# MCU_SWD_Program.net
KiCad netlist of a schematic drawn in Altium Designer
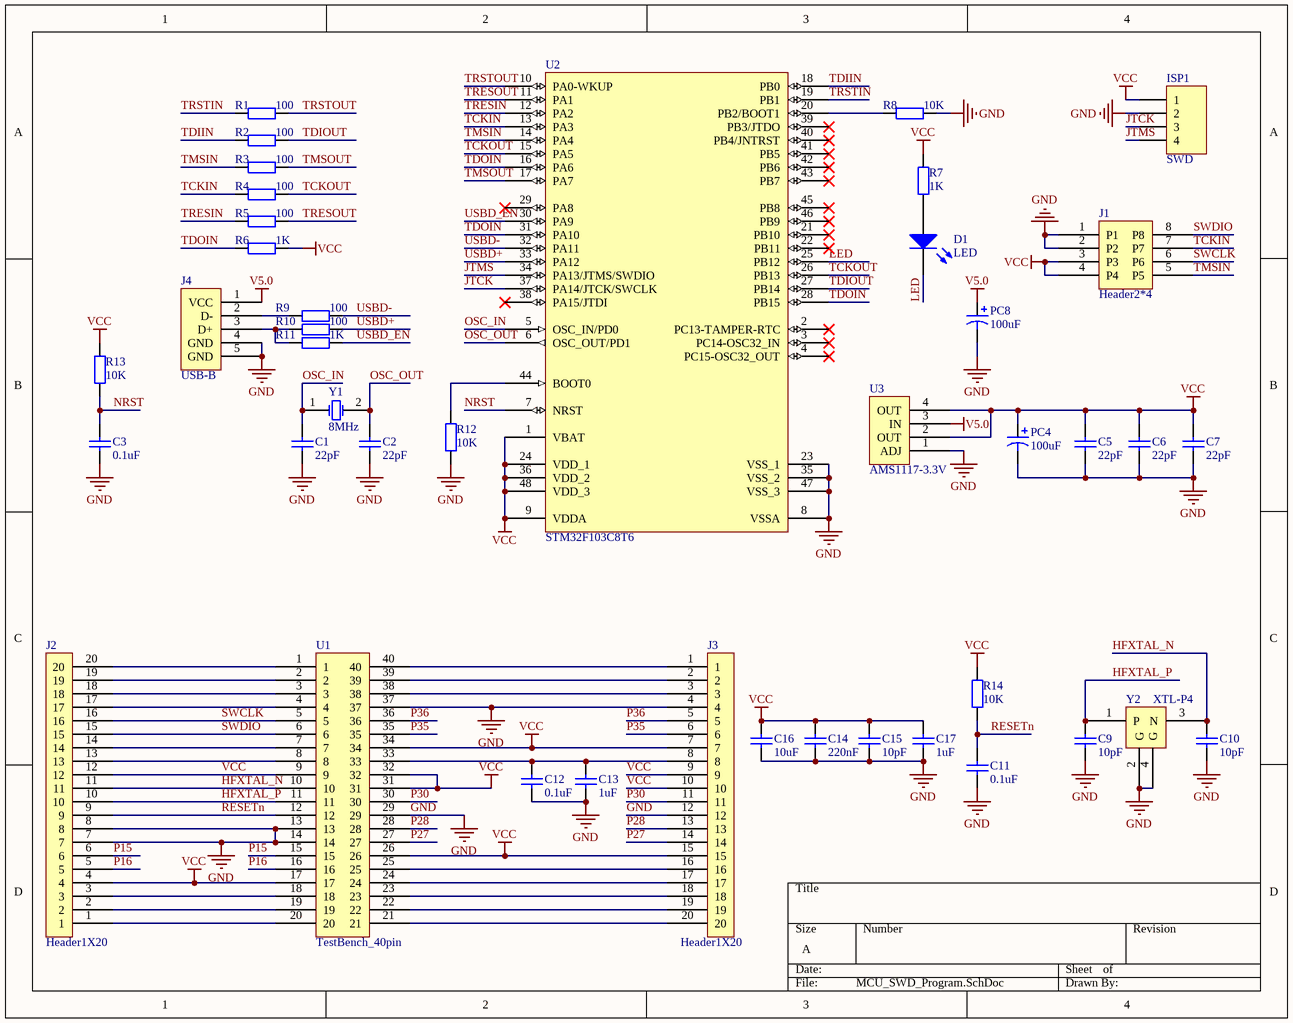
[diagram p0: MCU_SWD_Program.SchDoc]

(export (version "E")
  (design (tool "Eeschema 10.0.6"))
  (components
    (comp (ref "C1")
      (value "22pF")
      (footprint "C0603")
      (description "Capacitor")
      (fields (field (name "PUBLISHER") "Altium Limited"))
      (libsource (lib "Miscellaneous Devices") (part "Cap"))
    )
    (comp (ref "C2")
      (value "22pF")
      (footprint "C0603")
      (description "Capacitor")
      (fields (field (name "PUBLISHER") "Altium Limited"))
      (libsource (lib "Miscellaneous Devices") (part "Cap"))
    )
    (comp (ref "C3")
      (value "0.1uF")
      (footprint "C0603")
      (description "Capacitor")
      (fields (field (name "PUBLISHER") "Altium Limited"))
      (libsource (lib "Miscellaneous Devices") (part "Cap"))
    )
    (comp (ref "C5")
      (value "22pF")
      (footprint "C0603")
      (description "Capacitor")
      (fields (field (name "PUBLISHER") "Altium Limited"))
      (libsource (lib "Miscellaneous Devices") (part "Cap"))
    )
    (comp (ref "C6")
      (value "22pF")
      (footprint "C0603")
      (description "Capacitor")
      (fields (field (name "PUBLISHER") "Altium Limited"))
      (libsource (lib "Miscellaneous Devices") (part "Cap"))
    )
    (comp (ref "C7")
      (value "22pF")
      (footprint "C0603")
      (description "Capacitor")
      (fields (field (name "PUBLISHER") "Altium Limited"))
      (libsource (lib "Miscellaneous Devices") (part "Cap"))
    )
    (comp (ref "C9")
      (value "10pF")
      (footprint "C0603")
      (description "Capacitor")
      (fields (field (name "PUBLISHER") "Altium Limited"))
      (libsource (lib "Miscellaneous Devices") (part "Cap"))
    )
    (comp (ref "C10")
      (value "10pF")
      (footprint "C0603")
      (description "Capacitor")
      (fields (field (name "PUBLISHER") "Altium Limited"))
      (libsource (lib "Miscellaneous Devices") (part "Cap"))
    )
    (comp (ref "C11")
      (value "0.1uF")
      (footprint "C0603")
      (description "Capacitor")
      (fields (field (name "PUBLISHER") "Altium Limited"))
      (libsource (lib "Miscellaneous Devices") (part "Cap"))
    )
    (comp (ref "C12")
      (value "0.1uF")
      (footprint "C0603")
      (description "Capacitor")
      (fields (field (name "PUBLISHER") "Altium Limited"))
      (libsource (lib "Miscellaneous Devices") (part "Cap"))
    )
    (comp (ref "C13")
      (value "1uF")
      (footprint "C0603")
      (description "Capacitor")
      (fields (field (name "PUBLISHER") "Altium Limited"))
      (libsource (lib "Miscellaneous Devices") (part "Cap"))
    )
    (comp (ref "C14")
      (value "220nF")
      (footprint "C0603")
      (description "Capacitor")
      (fields (field (name "PUBLISHER") "Altium Limited"))
      (libsource (lib "Miscellaneous Devices") (part "Cap"))
    )
    (comp (ref "C15")
      (value "10pF")
      (footprint "C0603")
      (description "Capacitor")
      (fields (field (name "PUBLISHER") "Altium Limited"))
      (libsource (lib "Miscellaneous Devices") (part "Cap"))
    )
    (comp (ref "C16")
      (value "10uF")
      (footprint "C0603")
      (description "Capacitor")
      (fields (field (name "PUBLISHER") "Altium Limited"))
      (libsource (lib "Miscellaneous Devices") (part "Cap"))
    )
    (comp (ref "C17")
      (value "1uF")
      (footprint "C0603")
      (description "Capacitor")
      (fields (field (name "PUBLISHER") "Altium Limited"))
      (libsource (lib "Miscellaneous Devices") (part "Cap"))
    )
    (comp (ref "D1")
      (value "LED")
      (footprint "D-0805")
      (description "Typical RED, GREEN, YELLOW, AMBER GaAs LED")
      (fields (field (name "PUBLISHER") "Altium Limited"))
      (libsource (lib "Miscellaneous Devices") (part "LED2"))
    )
    (comp (ref "ISP1")
      (value "SWD")
      (footprint "HDR1X4")
      (description "Header, 4-Pin")
      (fields (field (name "PUBLISHER") "Altium Limited"))
      (libsource (lib "Miscellaneous Connectors") (part "Header 4"))
    )
    (comp (ref "J1")
      (value "Header2*4")
      (footprint "HDR2X4")
      (libsource (lib "GavinPCBLib") (part "Header2X4"))
    )
    (comp (ref "J2")
      (value "Header1X20")
      (footprint "HDR2.54-1X20")
      (libsource (lib "GavinPCBLib") (part "Header1X20"))
    )
    (comp (ref "J3")
      (value "Header1X20")
      (footprint "HDR2.54-1X20")
      (libsource (lib "") (part "Header1X20_1"))
    )
    (comp (ref "J4") (value "USB-B") (footprint "USB-B") (libsource (lib "GavinPCBLib") (part "USB-B")))
    (comp (ref "PC4")
      (value "100uF")
      (footprint "C1206")
      (description "Polarized Capacitor (Surface Mount)")
      (fields (field (name "PUBLISHER") "Altium Limited"))
      (libsource (lib "Miscellaneous Devices") (part "Cap Pol3"))
    )
    (comp (ref "PC8")
      (value "100uF")
      (footprint "C1206")
      (description "Polarized Capacitor (Surface Mount)")
      (fields (field (name "PUBLISHER") "Altium Limited"))
      (libsource (lib "Miscellaneous Devices") (part "Cap Pol3"))
    )
    (comp (ref "R1")
      (value "100")
      (footprint "R0603")
      (description "Resistor")
      (fields (field (name "PUBLISHER") "Altium Limited"))
      (libsource (lib "Miscellaneous Devices") (part "Res2"))
    )
    (comp (ref "R2")
      (value "100")
      (footprint "R0603")
      (description "Resistor")
      (fields (field (name "PUBLISHER") "Altium Limited"))
      (libsource (lib "Miscellaneous Devices") (part "Res2"))
    )
    (comp (ref "R3")
      (value "100")
      (footprint "R0603")
      (description "Resistor")
      (fields (field (name "PUBLISHER") "Altium Limited"))
      (libsource (lib "Miscellaneous Devices") (part "Res2"))
    )
    (comp (ref "R4")
      (value "100")
      (footprint "R0603")
      (description "Resistor")
      (fields (field (name "PUBLISHER") "Altium Limited"))
      (libsource (lib "Miscellaneous Devices") (part "Res2"))
    )
    (comp (ref "R5")
      (value "100")
      (footprint "R0603")
      (description "Resistor")
      (fields (field (name "PUBLISHER") "Altium Limited"))
      (libsource (lib "Miscellaneous Devices") (part "Res2"))
    )
    (comp (ref "R6")
      (value "1K")
      (footprint "r0603")
      (description "Resistor")
      (fields (field (name "PUBLISHER") "Altium Limited"))
      (libsource (lib "Miscellaneous Devices") (part "Res2"))
    )
    (comp (ref "R7")
      (value "1K")
      (footprint "R0603")
      (description "Resistor")
      (fields (field (name "PUBLISHER") "Altium Limited"))
      (libsource (lib "") (part "Res2_1"))
    )
    (comp (ref "R8")
      (value "10K")
      (footprint "R0603")
      (description "Resistor")
      (fields (field (name "PUBLISHER") "Altium Limited"))
      (libsource (lib "Miscellaneous Devices") (part "Res2"))
    )
    (comp (ref "R9")
      (value "100")
      (footprint "R0603")
      (description "Resistor")
      (fields (field (name "PUBLISHER") "Altium Limited"))
      (libsource (lib "Miscellaneous Devices") (part "Res2"))
    )
    (comp (ref "R10")
      (value "100")
      (footprint "R0603")
      (description "Resistor")
      (fields (field (name "PUBLISHER") "Altium Limited"))
      (libsource (lib "Miscellaneous Devices") (part "Res2"))
    )
    (comp (ref "R11")
      (value "1K")
      (footprint "R0603")
      (description "Resistor")
      (fields (field (name "PUBLISHER") "Altium Limited"))
      (libsource (lib "Miscellaneous Devices") (part "Res2"))
    )
    (comp (ref "R12")
      (value "10K")
      (footprint "R0603")
      (description "Resistor")
      (fields (field (name "PUBLISHER") "Altium Limited"))
      (libsource (lib "") (part "Res2_2"))
    )
    (comp (ref "R13")
      (value "10K")
      (footprint "R0603")
      (description "Resistor")
      (fields (field (name "PUBLISHER") "Altium Limited"))
      (libsource (lib "") (part "Res2_1"))
    )
    (comp (ref "R14")
      (value "10K")
      (footprint "R0603")
      (description "Resistor")
      (fields (field (name "PUBLISHER") "Altium Limited"))
      (libsource (lib "") (part "Res2_1"))
    )
    (comp (ref "U1")
      (value "TestBench_40pin")
      (footprint "DIP40")
      (libsource (lib "GavinPCBLib") (part "TestBench_40pin"))
    )
    (comp (ref "U2")
      (value "STM32F103C8T6")
      (footprint "LQFP-48")
      (libsource (lib "GavinPCBLib") (part "STM32F103C8T6"))
    )
    (comp (ref "U3")
      (value "AMS1117-3.3V")
      (footprint "SOT-223")
      (libsource (lib "GavinPCBLib") (part "AMS1117-3.3V"))
    )
    (comp (ref "Y1")
      (value "8MHz")
      (footprint "XTAL-SMD2")
      (description "Crystal Oscillator")
      (fields (field (name "PUBLISHER") "Altium Limited"))
      (libsource (lib "Miscellaneous Devices") (part "XTAL"))
    )
    (comp (ref "Y2") (value "XTL-P4") (footprint "X3225") (libsource (lib "GavinPCBLib") (part "XTL-P4")))
  )
  (nets
    (net (code "1") (name "/HFXTAL_N") (class "Default")
      (node (ref "C10") (pin "1") (pinfunction "1_1") (pintype "passive"))
      (node (ref "J2") (pin "11") (pinfunction "11_11") (pintype "passive"))
      (node (ref "U1") (pin "10") (pinfunction "10_10") (pintype "passive"))
      (node (ref "Y2") (pin "3") (pinfunction "N_3") (pintype "passive"))
    )
    (net (code "2") (name "/HFXTAL_P") (class "Default")
      (node (ref "C9") (pin "1") (pinfunction "1_1") (pintype "passive"))
      (node (ref "J2") (pin "10") (pinfunction "10_10") (pintype "passive"))
      (node (ref "U1") (pin "11") (pinfunction "11_11") (pintype "passive"))
      (node (ref "Y2") (pin "1") (pinfunction "P_1") (pintype "passive"))
    )
    (net (code "3") (name "/JTCK") (class "Default")
      (node (ref "ISP1") (pin "3") (pinfunction "3_3") (pintype "passive"))
      (node (ref "U2") (pin "37") (pinfunction "PA14/JTCK/SWCLK_37") (pintype "bidirectional"))
    )
    (net (code "4") (name "/JTMS") (class "Default")
      (node (ref "ISP1") (pin "4") (pinfunction "4_4") (pintype "passive"))
      (node (ref "U2") (pin "34") (pinfunction "PA13/JTMS/SWDIO_34") (pintype "bidirectional"))
    )
    (net (code "5") (name "/LED") (class "Default")
      (node (ref "D1") (pin "2") (pinfunction "K_2") (pintype "passive"))
      (node (ref "U2") (pin "25") (pinfunction "PB12_25") (pintype "bidirectional"))
    )
    (net (code "6") (name "/NRST") (class "Default")
      (node (ref "C3") (pin "1") (pinfunction "1_1") (pintype "passive"))
      (node (ref "R13") (pin "1") (pinfunction "1_1") (pintype "passive"))
      (node (ref "U2") (pin "7") (pinfunction "NRST_7") (pintype "bidirectional"))
    )
    (net (code "7") (name "/OSC_IN") (class "Default")
      (node (ref "C1") (pin "1") (pinfunction "1_1") (pintype "passive"))
      (node (ref "U2") (pin "5") (pinfunction "OSC_IN/PD0_5") (pintype "input"))
      (node (ref "Y1") (pin "1") (pinfunction "OSC1_1") (pintype "passive"))
    )
    (net (code "8") (name "/OSC_OUT") (class "Default")
      (node (ref "C2") (pin "1") (pinfunction "1_1") (pintype "passive"))
      (node (ref "U2") (pin "6") (pinfunction "OSC_OUT/PD1_6") (pintype "output"))
      (node (ref "Y1") (pin "2") (pinfunction "OSC2_2") (pintype "passive"))
    )
    (net (code "9") (name "/P15") (class "Default")
      (node (ref "J2") (pin "6") (pinfunction "6_6") (pintype "passive"))
      (node (ref "U1") (pin "15") (pinfunction "15_15") (pintype "passive"))
    )
    (net (code "10") (name "/P16") (class "Default")
      (node (ref "J2") (pin "5") (pinfunction "5_5") (pintype "passive"))
      (node (ref "U1") (pin "16") (pinfunction "16_16") (pintype "passive"))
    )
    (net (code "11") (name "/P27") (class "Default")
      (node (ref "J3") (pin "14") (pinfunction "14_14") (pintype "passive"))
      (node (ref "U1") (pin "27") (pinfunction "27_27") (pintype "passive"))
    )
    (net (code "12") (name "/P28") (class "Default")
      (node (ref "J3") (pin "13") (pinfunction "13_13") (pintype "passive"))
      (node (ref "U1") (pin "28") (pinfunction "28_28") (pintype "passive"))
    )
    (net (code "13") (name "/P30") (class "Default")
      (node (ref "J3") (pin "11") (pinfunction "11_11") (pintype "passive"))
      (node (ref "U1") (pin "30") (pinfunction "30_30") (pintype "passive"))
    )
    (net (code "14") (name "/P35") (class "Default")
      (node (ref "J3") (pin "6") (pinfunction "6_6") (pintype "passive"))
      (node (ref "U1") (pin "35") (pinfunction "35_35") (pintype "passive"))
    )
    (net (code "15") (name "/P36") (class "Default")
      (node (ref "J3") (pin "5") (pinfunction "5_5") (pintype "passive"))
      (node (ref "U1") (pin "36") (pinfunction "36_36") (pintype "passive"))
    )
    (net (code "16") (name "/RESETn") (class "Default")
      (node (ref "C11") (pin "1") (pinfunction "1_1") (pintype "passive"))
      (node (ref "J2") (pin "9") (pinfunction "9_9") (pintype "passive"))
      (node (ref "R14") (pin "1") (pinfunction "1_1") (pintype "passive"))
      (node (ref "U1") (pin "12") (pinfunction "12_12") (pintype "passive"))
    )
    (net (code "17") (name "/SWCLK") (class "Default")
      (node (ref "J1") (pin "6") (pinfunction "P6_6") (pintype "passive"))
      (node (ref "J2") (pin "16") (pinfunction "16_16") (pintype "passive"))
      (node (ref "U1") (pin "5") (pinfunction "5_5") (pintype "passive"))
    )
    (net (code "18") (name "/SWDIO") (class "Default")
      (node (ref "J1") (pin "8") (pinfunction "P8_8") (pintype "passive"))
      (node (ref "J2") (pin "15") (pinfunction "15_15") (pintype "passive"))
      (node (ref "U1") (pin "6") (pinfunction "6_6") (pintype "passive"))
    )
    (net (code "19") (name "/TCKIN") (class "Default")
      (node (ref "J1") (pin "7") (pinfunction "P7_7") (pintype "passive"))
      (node (ref "R4") (pin "1") (pinfunction "1_1") (pintype "passive"))
      (node (ref "U2") (pin "13") (pinfunction "PA3_13") (pintype "bidirectional"))
    )
    (net (code "20") (name "/TCKOUT") (class "Default")
      (node (ref "R4") (pin "2") (pinfunction "2_2") (pintype "passive"))
      (node (ref "U2") (pin "15") (pinfunction "PA5_15") (pintype "bidirectional"))
      (node (ref "U2") (pin "26") (pinfunction "PB13_26") (pintype "bidirectional"))
    )
    (net (code "21") (name "/TDIIN") (class "Default")
      (node (ref "R2") (pin "1") (pinfunction "1_1") (pintype "passive"))
      (node (ref "U2") (pin "18") (pinfunction "PB0_18") (pintype "bidirectional"))
    )
    (net (code "22") (name "/TDIOUT") (class "Default")
      (node (ref "R2") (pin "2") (pinfunction "2_2") (pintype "passive"))
      (node (ref "U2") (pin "27") (pinfunction "PB14_27") (pintype "bidirectional"))
    )
    (net (code "23") (name "/TDOIN") (class "Default")
      (node (ref "R6") (pin "1") (pinfunction "1_1") (pintype "passive"))
      (node (ref "U2") (pin "16") (pinfunction "PA6_16") (pintype "bidirectional"))
      (node (ref "U2") (pin "28") (pinfunction "PB15_28") (pintype "bidirectional"))
      (node (ref "U2") (pin "31") (pinfunction "PA10_31") (pintype "bidirectional"))
    )
    (net (code "24") (name "/TMSIN") (class "Default")
      (node (ref "J1") (pin "5") (pinfunction "P5_5") (pintype "passive"))
      (node (ref "R3") (pin "1") (pinfunction "1_1") (pintype "passive"))
      (node (ref "U2") (pin "14") (pinfunction "PA4_14") (pintype "bidirectional"))
    )
    (net (code "25") (name "/TMSOUT") (class "Default")
      (node (ref "R3") (pin "2") (pinfunction "2_2") (pintype "passive"))
      (node (ref "U2") (pin "17") (pinfunction "PA7_17") (pintype "bidirectional"))
    )
    (net (code "26") (name "/TRESIN") (class "Default")
      (node (ref "R5") (pin "1") (pinfunction "1_1") (pintype "passive"))
      (node (ref "U2") (pin "12") (pinfunction "PA2_12") (pintype "bidirectional"))
    )
    (net (code "27") (name "/TRESOUT") (class "Default")
      (node (ref "R5") (pin "2") (pinfunction "2_2") (pintype "passive"))
      (node (ref "U2") (pin "11") (pinfunction "PA1_11") (pintype "bidirectional"))
    )
    (net (code "28") (name "/TRSTIN") (class "Default")
      (node (ref "R1") (pin "1") (pinfunction "1_1") (pintype "passive"))
      (node (ref "U2") (pin "19") (pinfunction "PB1_19") (pintype "bidirectional"))
    )
    (net (code "29") (name "/TRSTOUT") (class "Default")
      (node (ref "R1") (pin "2") (pinfunction "2_2") (pintype "passive"))
      (node (ref "U2") (pin "10") (pinfunction "PA0-WKUP_10") (pintype "bidirectional"))
    )
    (net (code "30") (name "/USBD+") (class "Default")
      (node (ref "R10") (pin "2") (pinfunction "2_2") (pintype "passive"))
      (node (ref "U2") (pin "33") (pinfunction "PA12_33") (pintype "bidirectional"))
    )
    (net (code "31") (name "/USBD-") (class "Default")
      (node (ref "R9") (pin "2") (pinfunction "2_2") (pintype "passive"))
      (node (ref "U2") (pin "32") (pinfunction "PA11_32") (pintype "bidirectional"))
    )
    (net (code "32") (name "/USBD_EN") (class "Default")
      (node (ref "R11") (pin "2") (pinfunction "2_2") (pintype "passive"))
      (node (ref "U2") (pin "30") (pinfunction "PA9_30") (pintype "bidirectional"))
    )
    (net (code "33") (name "GND") (class "Default")
      (node (ref "C1") (pin "2") (pinfunction "2_2") (pintype "passive"))
      (node (ref "C10") (pin "2") (pinfunction "2_2") (pintype "passive"))
      (node (ref "C11") (pin "2") (pinfunction "2_2") (pintype "passive"))
      (node (ref "C12") (pin "2") (pinfunction "2_2") (pintype "passive"))
      (node (ref "C13") (pin "2") (pinfunction "2_2") (pintype "passive"))
      (node (ref "C14") (pin "2") (pinfunction "2_2") (pintype "passive"))
      (node (ref "C15") (pin "2") (pinfunction "2_2") (pintype "passive"))
      (node (ref "C16") (pin "2") (pinfunction "2_2") (pintype "passive"))
      (node (ref "C17") (pin "2") (pinfunction "2_2") (pintype "passive"))
      (node (ref "C2") (pin "2") (pinfunction "2_2") (pintype "passive"))
      (node (ref "C3") (pin "2") (pinfunction "2_2") (pintype "passive"))
      (node (ref "C5") (pin "2") (pinfunction "2_2") (pintype "passive"))
      (node (ref "C6") (pin "2") (pinfunction "2_2") (pintype "passive"))
      (node (ref "C7") (pin "2") (pinfunction "2_2") (pintype "passive"))
      (node (ref "C9") (pin "2") (pinfunction "2_2") (pintype "passive"))
      (node (ref "ISP1") (pin "2") (pinfunction "2_2") (pintype "passive"))
      (node (ref "J1") (pin "1") (pinfunction "P1_1") (pintype "passive"))
      (node (ref "J1") (pin "2") (pinfunction "P2_2") (pintype "passive"))
      (node (ref "J2") (pin "7") (pinfunction "7_7") (pintype "passive"))
      (node (ref "J2") (pin "8") (pinfunction "8_8") (pintype "passive"))
      (node (ref "J3") (pin "12") (pinfunction "12_12") (pintype "passive"))
      (node (ref "J3") (pin "4") (pinfunction "4_4") (pintype "passive"))
      (node (ref "J4") (pin "4") (pinfunction "GND_4") (pintype "passive"))
      (node (ref "J4") (pin "5") (pinfunction "GND_5") (pintype "passive"))
      (node (ref "PC4") (pin "2") (pinfunction "2_2") (pintype "passive"))
      (node (ref "PC8") (pin "2") (pinfunction "2_2") (pintype "passive"))
      (node (ref "R12") (pin "2") (pinfunction "2_2") (pintype "passive"))
      (node (ref "R8") (pin "2") (pinfunction "2_2") (pintype "passive"))
      (node (ref "U1") (pin "13") (pinfunction "13_13") (pintype "passive"))
      (node (ref "U1") (pin "14") (pinfunction "14_14") (pintype "passive"))
      (node (ref "U1") (pin "29") (pinfunction "29_29") (pintype "passive"))
      (node (ref "U1") (pin "37") (pinfunction "37_37") (pintype "passive"))
      (node (ref "U2") (pin "23") (pinfunction "VSS_1_23") (pintype "power_in"))
      (node (ref "U2") (pin "35") (pinfunction "VSS_2_35") (pintype "power_in"))
      (node (ref "U2") (pin "47") (pinfunction "VSS_3_47") (pintype "power_in"))
      (node (ref "U2") (pin "8") (pinfunction "VSSA_8") (pintype "power_in"))
      (node (ref "U3") (pin "1") (pinfunction "ADJ_1") (pintype "passive"))
      (node (ref "Y2") (pin "2") (pinfunction "G_2") (pintype "passive"))
      (node (ref "Y2") (pin "4") (pinfunction "G_4") (pintype "passive"))
    )
    (net (code "34") (name "Net-(C12-Pad1)") (class "Default")
      (node (ref "C12") (pin "1") (pinfunction "1_1") (pintype "passive"))
      (node (ref "C13") (pin "1") (pinfunction "1_1") (pintype "passive"))
      (node (ref "J3") (pin "8") (pinfunction "8_8") (pintype "passive"))
      (node (ref "U1") (pin "33") (pinfunction "33_33") (pintype "passive"))
    )
    (net (code "35") (name "Net-(D1-A)") (class "Default")
      (node (ref "D1") (pin "1") (pinfunction "A_1") (pintype "passive"))
      (node (ref "R7") (pin "1") (pinfunction "1_1") (pintype "passive"))
    )
    (net (code "36") (name "Net-(J2-Pad1)") (class "Default")
      (node (ref "J2") (pin "1") (pinfunction "1_1") (pintype "passive"))
      (node (ref "U1") (pin "20") (pinfunction "20_20") (pintype "passive"))
    )
    (net (code "37") (name "Net-(J2-Pad2)") (class "Default")
      (node (ref "J2") (pin "2") (pinfunction "2_2") (pintype "passive"))
      (node (ref "U1") (pin "19") (pinfunction "19_19") (pintype "passive"))
    )
    (net (code "38") (name "Net-(J2-Pad3)") (class "Default")
      (node (ref "J2") (pin "3") (pinfunction "3_3") (pintype "passive"))
      (node (ref "U1") (pin "18") (pinfunction "18_18") (pintype "passive"))
    )
    (net (code "39") (name "Net-(J2-Pad13)") (class "Default")
      (node (ref "J2") (pin "13") (pinfunction "13_13") (pintype "passive"))
      (node (ref "U1") (pin "8") (pinfunction "8_8") (pintype "passive"))
    )
    (net (code "40") (name "Net-(J2-Pad14)") (class "Default")
      (node (ref "J2") (pin "14") (pinfunction "14_14") (pintype "passive"))
      (node (ref "U1") (pin "7") (pinfunction "7_7") (pintype "passive"))
    )
    (net (code "41") (name "Net-(J2-Pad17)") (class "Default")
      (node (ref "J2") (pin "17") (pinfunction "17_17") (pintype "passive"))
      (node (ref "U1") (pin "4") (pinfunction "4_4") (pintype "passive"))
    )
    (net (code "42") (name "Net-(J2-Pad18)") (class "Default")
      (node (ref "J2") (pin "18") (pinfunction "18_18") (pintype "passive"))
      (node (ref "U1") (pin "3") (pinfunction "3_3") (pintype "passive"))
    )
    (net (code "43") (name "Net-(J2-Pad19)") (class "Default")
      (node (ref "J2") (pin "19") (pinfunction "19_19") (pintype "passive"))
      (node (ref "U1") (pin "2") (pinfunction "2_2") (pintype "passive"))
    )
    (net (code "44") (name "Net-(J2-Pad20)") (class "Default")
      (node (ref "J2") (pin "20") (pinfunction "20_20") (pintype "passive"))
      (node (ref "U1") (pin "1") (pinfunction "1_1") (pintype "passive"))
    )
    (net (code "45") (name "Net-(J3-Pad1)") (class "Default")
      (node (ref "J3") (pin "1") (pinfunction "1_1") (pintype "passive"))
      (node (ref "U1") (pin "40") (pinfunction "40_40") (pintype "passive"))
    )
    (net (code "46") (name "Net-(J3-Pad2)") (class "Default")
      (node (ref "J3") (pin "2") (pinfunction "2_2") (pintype "passive"))
      (node (ref "U1") (pin "39") (pinfunction "39_39") (pintype "passive"))
    )
    (net (code "47") (name "Net-(J3-Pad3)") (class "Default")
      (node (ref "J3") (pin "3") (pinfunction "3_3") (pintype "passive"))
      (node (ref "U1") (pin "38") (pinfunction "38_38") (pintype "passive"))
    )
    (net (code "48") (name "Net-(J3-Pad16)") (class "Default")
      (node (ref "J3") (pin "16") (pinfunction "16_16") (pintype "passive"))
      (node (ref "U1") (pin "25") (pinfunction "25_25") (pintype "passive"))
    )
    (net (code "49") (name "Net-(J3-Pad17)") (class "Default")
      (node (ref "J3") (pin "17") (pinfunction "17_17") (pintype "passive"))
      (node (ref "U1") (pin "24") (pinfunction "24_24") (pintype "passive"))
    )
    (net (code "50") (name "Net-(J3-Pad18)") (class "Default")
      (node (ref "J3") (pin "18") (pinfunction "18_18") (pintype "passive"))
      (node (ref "U1") (pin "23") (pinfunction "23_23") (pintype "passive"))
    )
    (net (code "51") (name "Net-(J3-Pad19)") (class "Default")
      (node (ref "J3") (pin "19") (pinfunction "19_19") (pintype "passive"))
      (node (ref "U1") (pin "22") (pinfunction "22_22") (pintype "passive"))
    )
    (net (code "52") (name "Net-(J3-Pad20)") (class "Default")
      (node (ref "J3") (pin "20") (pinfunction "20_20") (pintype "passive"))
      (node (ref "U1") (pin "21") (pinfunction "21_21") (pintype "passive"))
    )
    (net (code "53") (name "Net-(J4-D+)") (class "Default")
      (node (ref "J4") (pin "3") (pinfunction "D+_3") (pintype "passive"))
      (node (ref "R10") (pin "1") (pinfunction "1_1") (pintype "passive"))
      (node (ref "R11") (pin "1") (pinfunction "1_1") (pintype "passive"))
    )
    (net (code "54") (name "Net-(J4-D-)") (class "Default")
      (node (ref "J4") (pin "2") (pinfunction "D-_2") (pintype "passive"))
      (node (ref "R9") (pin "1") (pinfunction "1_1") (pintype "passive"))
    )
    (net (code "55") (name "Net-(U2-BOOT0)") (class "Default")
      (node (ref "R12") (pin "1") (pinfunction "1_1") (pintype "passive"))
      (node (ref "U2") (pin "44") (pinfunction "BOOT0_44") (pintype "input"))
    )
    (net (code "56") (name "Net-(U2-PB2{slash}BOOT1)") (class "Default")
      (node (ref "R8") (pin "1") (pinfunction "1_1") (pintype "passive"))
      (node (ref "U2") (pin "20") (pinfunction "PB2/BOOT1_20") (pintype "bidirectional"))
    )
    (net (code "57") (name "V5.0") (class "Default")
      (node (ref "J4") (pin "1") (pinfunction "VCC_1") (pintype "passive"))
      (node (ref "PC8") (pin "1") (pinfunction "1_1") (pintype "passive"))
      (node (ref "U3") (pin "3") (pinfunction "IN_3") (pintype "passive"))
    )
    (net (code "58") (name "VCC") (class "Default")
      (node (ref "C14") (pin "1") (pinfunction "1_1") (pintype "passive"))
      (node (ref "C15") (pin "1") (pinfunction "1_1") (pintype "passive"))
      (node (ref "C16") (pin "1") (pinfunction "1_1") (pintype "passive"))
      (node (ref "C17") (pin "1") (pinfunction "1_1") (pintype "passive"))
      (node (ref "C5") (pin "1") (pinfunction "1_1") (pintype "passive"))
      (node (ref "C6") (pin "1") (pinfunction "1_1") (pintype "passive"))
      (node (ref "C7") (pin "1") (pinfunction "1_1") (pintype "passive"))
      (node (ref "ISP1") (pin "1") (pinfunction "1_1") (pintype "passive"))
      (node (ref "J1") (pin "3") (pinfunction "P3_3") (pintype "passive"))
      (node (ref "J1") (pin "4") (pinfunction "P4_4") (pintype "passive"))
      (node (ref "J2") (pin "12") (pinfunction "12_12") (pintype "passive"))
      (node (ref "J2") (pin "4") (pinfunction "4_4") (pintype "passive"))
      (node (ref "J3") (pin "10") (pinfunction "10_10") (pintype "passive"))
      (node (ref "J3") (pin "15") (pinfunction "15_15") (pintype "passive"))
      (node (ref "J3") (pin "7") (pinfunction "7_7") (pintype "passive"))
      (node (ref "J3") (pin "9") (pinfunction "9_9") (pintype "passive"))
      (node (ref "PC4") (pin "1") (pinfunction "1_1") (pintype "passive"))
      (node (ref "R13") (pin "2") (pinfunction "2_2") (pintype "passive"))
      (node (ref "R14") (pin "2") (pinfunction "2_2") (pintype "passive"))
      (node (ref "R6") (pin "2") (pinfunction "2_2") (pintype "passive"))
      (node (ref "R7") (pin "2") (pinfunction "2_2") (pintype "passive"))
      (node (ref "U1") (pin "17") (pinfunction "17_17") (pintype "passive"))
      (node (ref "U1") (pin "26") (pinfunction "26_26") (pintype "passive"))
      (node (ref "U1") (pin "31") (pinfunction "31_31") (pintype "passive"))
      (node (ref "U1") (pin "32") (pinfunction "32_32") (pintype "passive"))
      (node (ref "U1") (pin "34") (pinfunction "34_34") (pintype "passive"))
      (node (ref "U1") (pin "9") (pinfunction "9_9") (pintype "passive"))
      (node (ref "U2") (pin "1") (pinfunction "VBAT_1") (pintype "power_in"))
      (node (ref "U2") (pin "24") (pinfunction "VDD_1_24") (pintype "power_in"))
      (node (ref "U2") (pin "36") (pinfunction "VDD_2_36") (pintype "power_in"))
      (node (ref "U2") (pin "48") (pinfunction "VDD_3_48") (pintype "power_in"))
      (node (ref "U2") (pin "9") (pinfunction "VDDA_9") (pintype "power_in"))
      (node (ref "U3") (pin "2") (pinfunction "OUT_2") (pintype "passive"))
      (node (ref "U3") (pin "4") (pinfunction "OUT_4") (pintype "passive"))
    )
    (net (code "59") (name "unconnected-(U2-PA8-Pad29)") (class "Default")
      (node (ref "U2") (pin "29") (pinfunction "PA8_29") (pintype "bidirectional+no_connect"))
    )
    (net (code "60") (name "unconnected-(U2-PA15{slash}JTDI-Pad38)") (class "Default")
      (node (ref "U2") (pin "38") (pinfunction "PA15/JTDI_38") (pintype "bidirectional+no_connect"))
    )
    (net (code "61") (name "unconnected-(U2-PB3{slash}JTDO-Pad39)") (class "Default")
      (node (ref "U2") (pin "39") (pinfunction "PB3/JTDO_39") (pintype "bidirectional+no_connect"))
    )
    (net (code "62") (name "unconnected-(U2-PB4{slash}JNTRST-Pad40)") (class "Default")
      (node (ref "U2") (pin "40") (pinfunction "PB4/JNTRST_40") (pintype "bidirectional+no_connect"))
    )
    (net (code "63") (name "unconnected-(U2-PB5-Pad41)") (class "Default")
      (node (ref "U2") (pin "41") (pinfunction "PB5_41") (pintype "bidirectional+no_connect"))
    )
    (net (code "64") (name "unconnected-(U2-PB6-Pad42)") (class "Default")
      (node (ref "U2") (pin "42") (pinfunction "PB6_42") (pintype "bidirectional+no_connect"))
    )
    (net (code "65") (name "unconnected-(U2-PB7-Pad43)") (class "Default")
      (node (ref "U2") (pin "43") (pinfunction "PB7_43") (pintype "bidirectional+no_connect"))
    )
    (net (code "66") (name "unconnected-(U2-PB8-Pad45)") (class "Default")
      (node (ref "U2") (pin "45") (pinfunction "PB8_45") (pintype "bidirectional+no_connect"))
    )
    (net (code "67") (name "unconnected-(U2-PB9-Pad46)") (class "Default")
      (node (ref "U2") (pin "46") (pinfunction "PB9_46") (pintype "bidirectional+no_connect"))
    )
    (net (code "68") (name "unconnected-(U2-PB10-Pad21)") (class "Default")
      (node (ref "U2") (pin "21") (pinfunction "PB10_21") (pintype "bidirectional+no_connect"))
    )
    (net (code "69") (name "unconnected-(U2-PB11-Pad22)") (class "Default")
      (node (ref "U2") (pin "22") (pinfunction "PB11_22") (pintype "bidirectional+no_connect"))
    )
    (net (code "70") (name "unconnected-(U2-PC13-TAMPER-RTC-Pad2)") (class "Default")
      (node (ref "U2") (pin "2") (pinfunction "PC13-TAMPER-RTC_2") (pintype "bidirectional+no_connect"))
    )
    (net (code "71") (name "unconnected-(U2-PC14-OSC32_IN-Pad3)") (class "Default")
      (node (ref "U2") (pin "3") (pinfunction "PC14-OSC32_IN_3") (pintype "bidirectional+no_connect"))
    )
    (net (code "72") (name "unconnected-(U2-PC15-OSC32_OUT-Pad4)") (class "Default")
      (node (ref "U2") (pin "4") (pinfunction "PC15-OSC32_OUT_4") (pintype "bidirectional+no_connect"))
    )
  )
)
